# usb_dcdc_12v_power.net
KiCad netlist of a schematic drawn in EAGLE
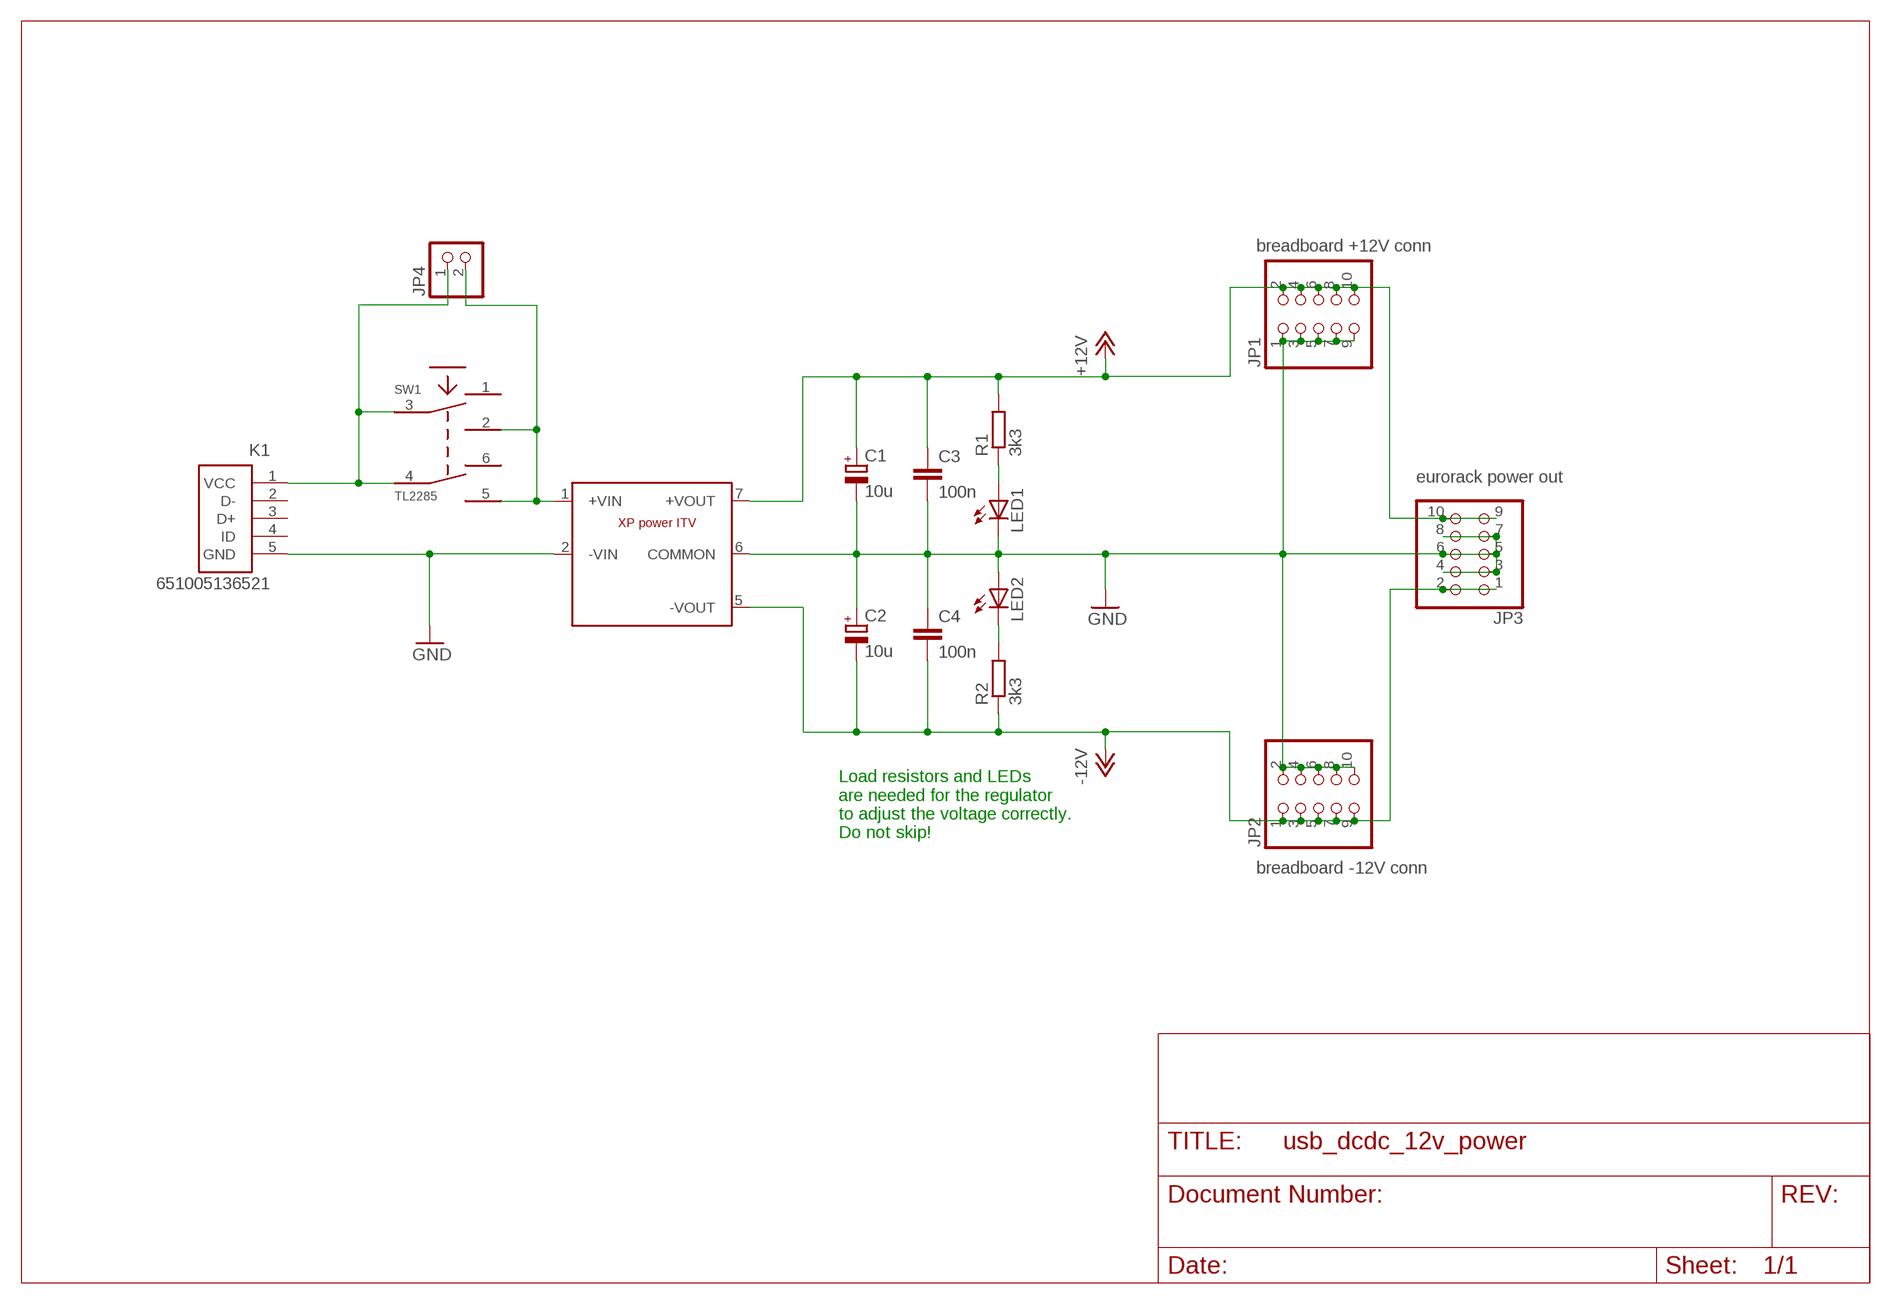
[diagram p0: schematic, sheet 1]

(export (version "E")
  (design (tool "Eeschema 10.0.6"))
  (components
    (comp (ref "C1")
      (value "10u")
      (footprint "eagle-import:E2,5-5")
      (libsource (lib "eagle-import") (part "CPOL-EUE2.5-5"))
    )
    (comp (ref "C2")
      (value "10u")
      (footprint "eagle-import:E2,5-5")
      (libsource (lib "eagle-import") (part "CPOL-EUE2.5-5"))
    )
    (comp (ref "C3")
      (value "100n")
      (footprint "eagle-import:C025-025X050")
      (libsource (lib "eagle-import") (part "C-EU025-025X050"))
    )
    (comp (ref "C4")
      (value "100n")
      (footprint "eagle-import:C025-025X050")
      (libsource (lib "eagle-import") (part "C-EU025-025X050"))
    )
    (comp (ref "JP1")
      (value "breadboard +12V conn")
      (footprint "eagle-import:2X05")
      (libsource (lib "eagle-import") (part "PINHD-2X5"))
    )
    (comp (ref "JP2")
      (value "breadboard -12V conn")
      (footprint "eagle-import:2X05")
      (libsource (lib "eagle-import") (part "PINHD-2X5"))
    )
    (comp (ref "JP3")
      (value "eurorack power out")
      (footprint "eagle-import:2X05")
      (libsource (lib "eagle-import") (part "PINHD-2X5"))
    )
    (comp (ref "JP4")
      (value "PINHD-1X2")
      (footprint "eagle-import:1X02")
      (libsource (lib "eagle-import") (part "PINHD-1X2"))
    )
    (comp (ref "K1")
      (value "651005136521")
      (footprint "eagle-import:651005136521")
      (libsource (lib "eagle-import") (part "651005136521"))
    )
    (comp (ref "LED1")
      (value "LED3MM")
      (footprint "eagle-import:LED3MM")
      (libsource (lib "eagle-import") (part "LED3MM"))
    )
    (comp (ref "LED2")
      (value "LED3MM")
      (footprint "eagle-import:LED3MM")
      (libsource (lib "eagle-import") (part "LED3MM"))
    )
    (comp (ref "R1")
      (value "3k3")
      (footprint "eagle-import:0207_2V")
      (libsource (lib "eagle-import") (part "R-EU_0207/2V"))
    )
    (comp (ref "R2")
      (value "3k3")
      (footprint "eagle-import:0207_2V")
      (libsource (lib "eagle-import") (part "R-EU_0207/2V"))
    )
    (comp (ref "SW1")
      (value "TL2285")
      (footprint "eagle-import:TL2285_PCB")
      (libsource (lib "eagle-import") (part "TL2285"))
    )
    (comp (ref "U$1")
      (value "XP_POWER_ITV")
      (footprint "eagle-import:DC_CONV_SIP_STD")
      (libsource (lib "eagle-import") (part "XP_POWER_ITV"))
    )
  )
  (nets
    (net (code "1") (name "+12V") (class "Default")
      (node (ref "C1") (pin "+") (pinfunction "+_+") (pintype "passive"))
      (node (ref "C3") (pin "1") (pinfunction "1_1") (pintype "passive"))
      (node (ref "JP1") (pin "10") (pinfunction "10_10") (pintype "passive"))
      (node (ref "JP1") (pin "2") (pinfunction "2_2") (pintype "passive"))
      (node (ref "JP1") (pin "4") (pinfunction "4_4") (pintype "passive"))
      (node (ref "JP1") (pin "6") (pinfunction "6_6") (pintype "passive"))
      (node (ref "JP1") (pin "8") (pinfunction "8_8") (pintype "passive"))
      (node (ref "JP3") (pin "10") (pinfunction "10_10") (pintype "passive"))
      (node (ref "JP3") (pin "9") (pinfunction "9_9") (pintype "passive"))
      (node (ref "R1") (pin "2") (pinfunction "2_2") (pintype "passive"))
      (node (ref "U$1") (pin "7") (pinfunction "+VOUT_7") (pintype "bidirectional"))
    )
    (net (code "2") (name "-12V") (class "Default")
      (node (ref "C2") (pin "-") (pinfunction "-_-") (pintype "passive"))
      (node (ref "C4") (pin "2") (pinfunction "2_2") (pintype "passive"))
      (node (ref "JP2") (pin "1") (pinfunction "1_1") (pintype "passive"))
      (node (ref "JP2") (pin "3") (pinfunction "3_3") (pintype "passive"))
      (node (ref "JP2") (pin "5") (pinfunction "5_5") (pintype "passive"))
      (node (ref "JP2") (pin "7") (pinfunction "7_7") (pintype "passive"))
      (node (ref "JP2") (pin "9") (pinfunction "9_9") (pintype "passive"))
      (node (ref "JP3") (pin "1") (pinfunction "1_1") (pintype "passive"))
      (node (ref "JP3") (pin "2") (pinfunction "2_2") (pintype "passive"))
      (node (ref "R2") (pin "1") (pinfunction "1_1") (pintype "passive"))
      (node (ref "U$1") (pin "5") (pinfunction "-VOUT_5") (pintype "bidirectional"))
    )
    (net (code "3") (name "GND") (class "Default")
      (node (ref "C1") (pin "-") (pinfunction "-_-") (pintype "passive"))
      (node (ref "C2") (pin "+") (pinfunction "+_+") (pintype "passive"))
      (node (ref "C3") (pin "2") (pinfunction "2_2") (pintype "passive"))
      (node (ref "C4") (pin "1") (pinfunction "1_1") (pintype "passive"))
      (node (ref "JP1") (pin "1") (pinfunction "1_1") (pintype "passive"))
      (node (ref "JP1") (pin "3") (pinfunction "3_3") (pintype "passive"))
      (node (ref "JP1") (pin "5") (pinfunction "5_5") (pintype "passive"))
      (node (ref "JP1") (pin "7") (pinfunction "7_7") (pintype "passive"))
      (node (ref "JP1") (pin "9") (pinfunction "9_9") (pintype "passive"))
      (node (ref "JP2") (pin "10") (pinfunction "10_10") (pintype "passive"))
      (node (ref "JP2") (pin "2") (pinfunction "2_2") (pintype "passive"))
      (node (ref "JP2") (pin "4") (pinfunction "4_4") (pintype "passive"))
      (node (ref "JP2") (pin "6") (pinfunction "6_6") (pintype "passive"))
      (node (ref "JP2") (pin "8") (pinfunction "8_8") (pintype "passive"))
      (node (ref "JP3") (pin "3") (pinfunction "3_3") (pintype "passive"))
      (node (ref "JP3") (pin "4") (pinfunction "4_4") (pintype "passive"))
      (node (ref "JP3") (pin "5") (pinfunction "5_5") (pintype "passive"))
      (node (ref "JP3") (pin "6") (pinfunction "6_6") (pintype "passive"))
      (node (ref "JP3") (pin "7") (pinfunction "7_7") (pintype "passive"))
      (node (ref "JP3") (pin "8") (pinfunction "8_8") (pintype "passive"))
      (node (ref "K1") (pin "5") (pinfunction "GND_5") (pintype "passive"))
      (node (ref "LED1") (pin "K") (pinfunction "C_K") (pintype "passive"))
      (node (ref "LED2") (pin "A") (pinfunction "A_A") (pintype "passive"))
      (node (ref "U$1") (pin "2") (pinfunction "-VIN_2") (pintype "bidirectional"))
      (node (ref "U$1") (pin "6") (pinfunction "COMMON_6") (pintype "bidirectional"))
    )
    (net (code "4") (name "Net-(K1-VCC)") (class "Default")
      (node (ref "JP4") (pin "1") (pinfunction "1_1") (pintype "passive"))
      (node (ref "K1") (pin "1") (pinfunction "VCC_1") (pintype "passive"))
      (node (ref "SW1") (pin "3") (pinfunction "P3_3") (pintype "bidirectional"))
      (node (ref "SW1") (pin "4") (pinfunction "P4_4") (pintype "bidirectional"))
    )
    (net (code "5") (name "Net-(LED1-PadA)") (class "Default")
      (node (ref "LED1") (pin "A") (pinfunction "A_A") (pintype "passive"))
      (node (ref "R1") (pin "1") (pinfunction "1_1") (pintype "passive"))
    )
    (net (code "6") (name "Net-(LED2-C)") (class "Default")
      (node (ref "LED2") (pin "K") (pinfunction "C_K") (pintype "passive"))
      (node (ref "R2") (pin "2") (pinfunction "2_2") (pintype "passive"))
    )
    (net (code "7") (name "Net-(SW1-P2)") (class "Default")
      (node (ref "JP4") (pin "2") (pinfunction "2_2") (pintype "passive"))
      (node (ref "SW1") (pin "2") (pinfunction "P2_2") (pintype "bidirectional"))
      (node (ref "SW1") (pin "5") (pinfunction "P5_5") (pintype "bidirectional"))
      (node (ref "U$1") (pin "1") (pinfunction "+VIN_1") (pintype "bidirectional"))
    )
    (net (code "8") (name "unconnected-(K1-D+-Pad3)") (class "Default")
      (node (ref "K1") (pin "3") (pinfunction "D+_3") (pintype "passive"))
    )
    (net (code "9") (name "unconnected-(K1-D--Pad2)") (class "Default")
      (node (ref "K1") (pin "2") (pinfunction "D-_2") (pintype "passive"))
    )
    (net (code "10") (name "unconnected-(K1-ID-Pad4)") (class "Default")
      (node (ref "K1") (pin "4") (pinfunction "ID_4") (pintype "passive"))
    )
    (net (code "11") (name "unconnected-(SW1-P1-Pad1)") (class "Default")
      (node (ref "SW1") (pin "1") (pinfunction "P1_1") (pintype "bidirectional"))
    )
    (net (code "12") (name "unconnected-(SW1-P6-Pad6)") (class "Default")
      (node (ref "SW1") (pin "6") (pinfunction "P6_6") (pintype "bidirectional"))
    )
  )
)
